# siren.net
KiCad netlist of a schematic drawn in EAGLE
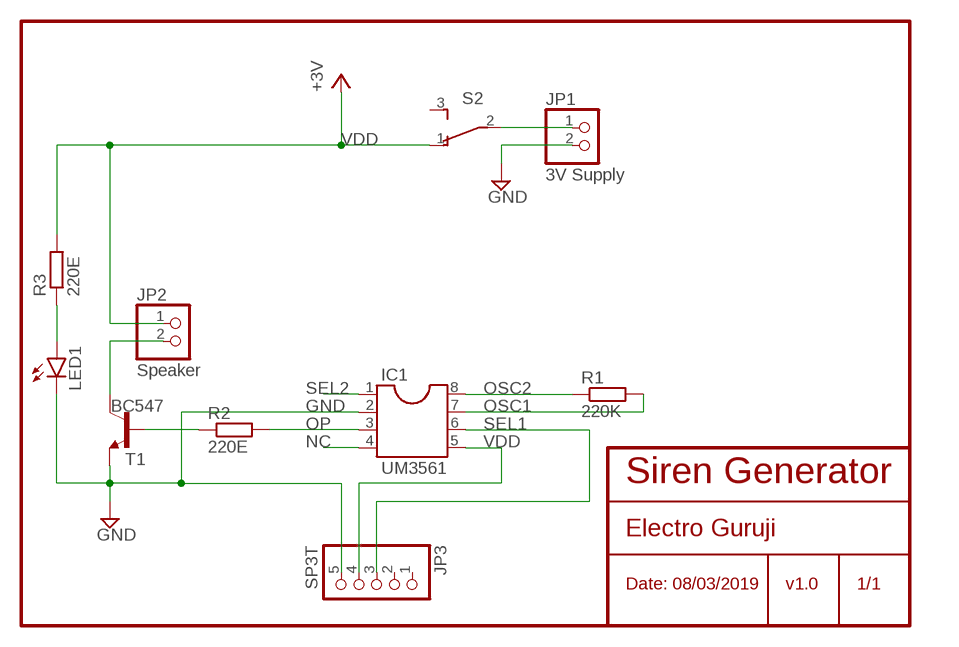
[diagram p0: schematic, sheet 1]

(export (version "E")
  (design (tool "Eeschema 10.0.6"))
  (components
    (comp (ref "IC1")
      (value "UM3561")
      (footprint "eagle-import:SOCKET-08")
      (libsource (lib "eagle-import") (part "DIL8S"))
    )
    (comp (ref "JP1")
      (value "3V Supply")
      (footprint "eagle-import:1X02")
      (fields (field (name "SPICEPREFIX") "B"))
      (libsource (lib "eagle-import") (part "PINHD-1X2"))
    )
    (comp (ref "JP2")
      (value "Speaker")
      (footprint "eagle-import:1X02")
      (libsource (lib "eagle-import") (part "PINHD-1X2"))
    )
    (comp (ref "JP3")
      (value "SP3T")
      (footprint "eagle-import:1X05")
      (libsource (lib "eagle-import") (part "PINHD-1X5"))
    )
    (comp (ref "LED1")
      (value "LED5MM")
      (footprint "eagle-import:LED5MM")
      (libsource (lib "eagle-import") (part "LED5MM"))
    )
    (comp (ref "R1")
      (value "220K")
      (footprint "eagle-import:0204_5")
      (libsource (lib "eagle-import") (part "R-EU_0204/5"))
    )
    (comp (ref "R2")
      (value "220E")
      (footprint "eagle-import:0204_5")
      (libsource (lib "eagle-import") (part "R-EU_0204/5"))
    )
    (comp (ref "R3")
      (value "220E")
      (footprint "eagle-import:0204_5")
      (libsource (lib "eagle-import") (part "R-EU_0204/5"))
    )
    (comp (ref "S2")
      (value "TL36YO")
      (footprint "eagle-import:TL3XYO")
      (libsource (lib "eagle-import") (part "TL36YO"))
    )
    (comp (ref "T1")
      (value "BC547")
      (footprint "eagle-import:TO92-EBC")
      (libsource (lib "eagle-import") (part "-NPN-TO92-EBC"))
    )
  )
  (nets
    (net (code "1") (name "+3V") (class "Default")
      (node (ref "IC1") (pin "5") (pinfunction "5_5") (pintype "passive"))
      (node (ref "JP2") (pin "1") (pinfunction "1_1") (pintype "passive"))
      (node (ref "JP3") (pin "4") (pinfunction "4_4") (pintype "passive"))
      (node (ref "R3") (pin "2") (pinfunction "2_2") (pintype "passive"))
      (node (ref "S2") (pin "1") (pinfunction "O_1") (pintype "passive"))
    )
    (net (code "2") (name "/NC") (class "Default")
      (node (ref "IC1") (pin "4") (pinfunction "4_4") (pintype "passive"))
    )
    (net (code "3") (name "/OP") (class "Default")
      (node (ref "IC1") (pin "3") (pinfunction "3_3") (pintype "passive"))
      (node (ref "R2") (pin "2") (pinfunction "2_2") (pintype "passive"))
    )
    (net (code "4") (name "/OSC1") (class "Default")
      (node (ref "IC1") (pin "7") (pinfunction "7_7") (pintype "passive"))
      (node (ref "R1") (pin "2") (pinfunction "2_2") (pintype "passive"))
    )
    (net (code "5") (name "/OSC2") (class "Default")
      (node (ref "IC1") (pin "8") (pinfunction "8_8") (pintype "passive"))
      (node (ref "R1") (pin "1") (pinfunction "1_1") (pintype "passive"))
    )
    (net (code "6") (name "/SEL1") (class "Default")
      (node (ref "IC1") (pin "6") (pinfunction "6_6") (pintype "passive"))
      (node (ref "JP3") (pin "3") (pinfunction "3_3") (pintype "passive"))
    )
    (net (code "7") (name "/SEL2") (class "Default")
      (node (ref "IC1") (pin "1") (pinfunction "1_1") (pintype "passive"))
    )
    (net (code "8") (name "GND") (class "Default")
      (node (ref "IC1") (pin "2") (pinfunction "2_2") (pintype "passive"))
      (node (ref "JP1") (pin "2") (pinfunction "2_2") (pintype "passive"))
      (node (ref "JP3") (pin "5") (pinfunction "5_5") (pintype "passive"))
      (node (ref "LED1") (pin "K") (pinfunction "C_K") (pintype "passive"))
      (node (ref "T1") (pin "E") (pinfunction "E_E") (pintype "passive"))
    )
    (net (code "9") (name "Net-(JP2-Pad2)") (class "Default")
      (node (ref "JP2") (pin "2") (pinfunction "2_2") (pintype "passive"))
      (node (ref "T1") (pin "C") (pinfunction "C_C") (pintype "passive"))
    )
    (net (code "10") (name "Net-(LED1-PadA)") (class "Default")
      (node (ref "LED1") (pin "A") (pinfunction "A_A") (pintype "passive"))
      (node (ref "R3") (pin "1") (pinfunction "1_1") (pintype "passive"))
    )
    (net (code "11") (name "Net-(R2-Pad1)") (class "Default")
      (node (ref "R2") (pin "1") (pinfunction "1_1") (pintype "passive"))
      (node (ref "T1") (pin "B") (pinfunction "B_B") (pintype "passive"))
    )
    (net (code "12") (name "Net-(S2-P)") (class "Default")
      (node (ref "JP1") (pin "1") (pinfunction "1_1") (pintype "passive"))
      (node (ref "S2") (pin "2") (pinfunction "P_2") (pintype "passive"))
    )
    (net (code "13") (name "unconnected-(JP3-Pad1)") (class "Default")
      (node (ref "JP3") (pin "1") (pinfunction "1_1") (pintype "passive"))
    )
    (net (code "14") (name "unconnected-(JP3-Pad2)") (class "Default")
      (node (ref "JP3") (pin "2") (pinfunction "2_2") (pintype "passive"))
    )
    (net (code "15") (name "unconnected-(S2-S-Pad3)") (class "Default")
      (node (ref "S2") (pin "3") (pinfunction "S_3") (pintype "passive"))
    )
  )
)
